# NRF52840_MICRO.net
KiCad netlist of a schematic drawn in Altium Designer
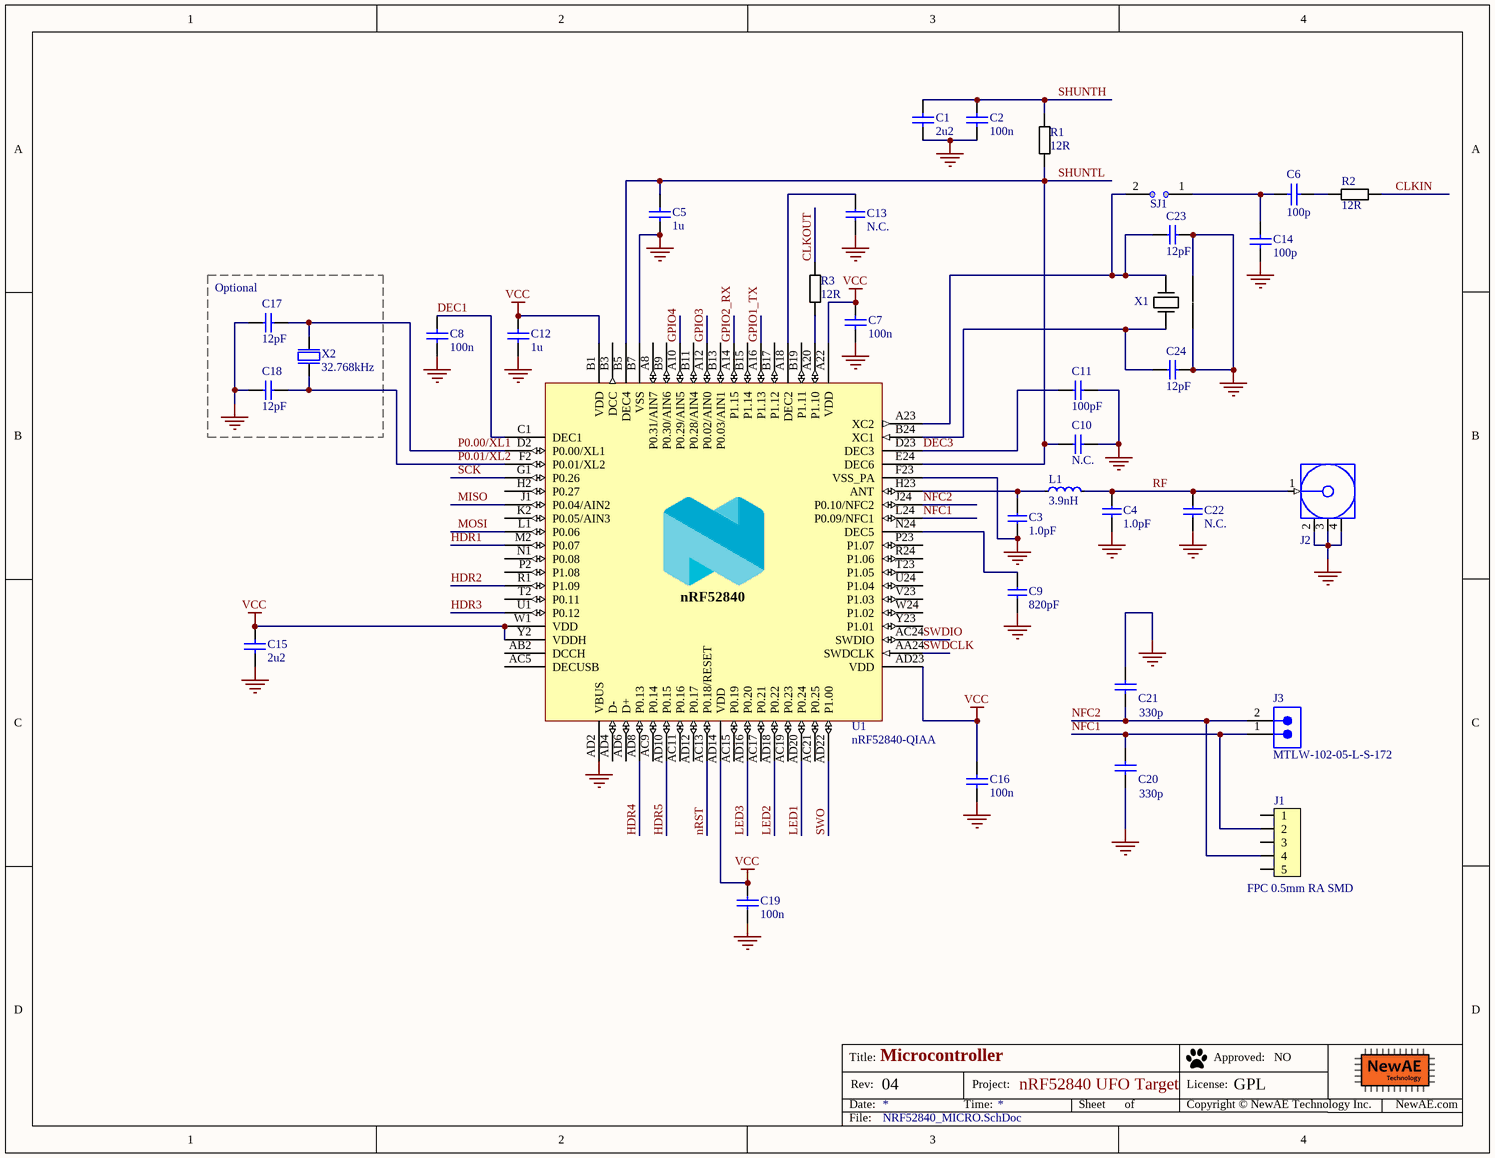
[diagram p0: NRF52840_MICRO.SchDoc]

(export (version "E")
  (design (tool "Eeschema 10.0.6"))
  (components
    (comp (ref "C1")
      (value "2u2")
      (footprint "CAPC0603_M")
      (description "2u2, 0603")
      (fields (field (name "PART NUMBER") "CCHIP-2u2-0603"))
      (libsource (lib "NewAE_AltiumLib") (part "CAP"))
    )
    (comp (ref "C2")
      (value "100n")
      (footprint "CAPC0603_M")
      (description "100n, 0603")
      (fields (field (name "PART NUMBER") "CCHIP-100n-0603"))
      (libsource (lib "NewAE_AltiumLib") (part "CAP"))
    )
    (comp (ref "C3")
      (value "1.0pF")
      (footprint "CAPC1005X04L")
      (description "Capacitor, NP0, ±5%")
      (fields (field (name "PART NUMBER") "C0402-1.0p") (field (name "PUBLISHER") "Nordic Semiconductor"))
      (libsource (lib "Nordic Passive DB") (part "CAP"))
    )
    (comp (ref "C4")
      (value "1.0pF")
      (footprint "CAPC1005X04L")
      (description "Capacitor, NP0, ±5%")
      (fields (field (name "PART NUMBER") "C0402-1.0p") (field (name "PUBLISHER") "Nordic Semiconductor"))
      (libsource (lib "Nordic Passive DB") (part "CAP"))
    )
    (comp (ref "C5")
      (value "1u")
      (footprint "CAPC0603_M")
      (description "1u, 0603, 50V")
      (fields (field (name "PART NUMBER") "CCHIP-1u-0603"))
      (libsource (lib "NewAE_AltiumLib") (part "CAP"))
    )
    (comp (ref "C6")
      (value "100p")
      (footprint "CAPC0603_M")
      (description "100p, 0603")
      (fields (field (name "PART NUMBER") "CCHIP-100p-0603"))
      (libsource (lib "NewAE_AltiumLib") (part "CAP"))
    )
    (comp (ref "C7")
      (value "100n")
      (footprint "CAPC0603_M")
      (description "100n, 0603")
      (fields (field (name "PART NUMBER") "CCHIP-100n-0603"))
      (libsource (lib "NewAE_AltiumLib") (part "CAP"))
    )
    (comp (ref "C8")
      (value "100n")
      (footprint "CAPC0603_M")
      (description "100n, 0603")
      (fields (field (name "PART NUMBER") "CCHIP-100n-0603"))
      (libsource (lib "NewAE_AltiumLib") (part "CAP"))
    )
    (comp (ref "C9")
      (value "820pF")
      (footprint "CAPC1005X04L")
      (description "Capacitor, NP0, ±5%")
      (fields (field (name "PART NUMBER") "C0402-820p") (field (name "PUBLISHER") "Nordic Semiconductor"))
      (libsource (lib "Nordic Passive DB") (part "CAP"))
    )
    (comp (ref "C10")
      (value "N.C.")
      (footprint "CAPC1005X04L")
      (description "Not mounted")
      (fields (field (name "PART NUMBER") "C0402-N.C.") (field (name "PUBLISHER") "Nordic Semiconductor"))
      (libsource (lib "Nordic Passive DB") (part "CAP"))
    )
    (comp (ref "C11")
      (value "100pF")
      (footprint "CAPC1005X04L")
      (description "Capacitor, NP0, ±5%")
      (fields (field (name "PART NUMBER") "C0402-100p") (field (name "PUBLISHER") "Nordic Semiconductor"))
      (libsource (lib "Nordic Passive DB") (part "CAP"))
    )
    (comp (ref "C12")
      (value "1u")
      (footprint "CAPC0603_M")
      (description "1u, 0603, 50V")
      (fields (field (name "PART NUMBER") "CCHIP-1u-0603"))
      (libsource (lib "NewAE_AltiumLib") (part "CAP"))
    )
    (comp (ref "C13")
      (value "N.C.")
      (footprint "CAPC1005X04L")
      (description "Not mounted")
      (fields (field (name "PART NUMBER") "C0402-N.C.") (field (name "PUBLISHER") "Nordic Semiconductor"))
      (libsource (lib "Nordic Passive DB") (part "CAP"))
    )
    (comp (ref "C14")
      (value "100p")
      (footprint "CAPC0603_M")
      (description "100p, 0603")
      (fields (field (name "PART NUMBER") "CCHIP-100p-0603"))
      (libsource (lib "NewAE_AltiumLib") (part "CAP"))
    )
    (comp (ref "C15")
      (value "2u2")
      (footprint "CAPC0603_M")
      (description "2u2, 0603")
      (fields (field (name "PART NUMBER") "CCHIP-2u2-0603"))
      (libsource (lib "NewAE_AltiumLib") (part "CAP"))
    )
    (comp (ref "C16")
      (value "100n")
      (footprint "CAPC0603_M")
      (description "100n, 0603")
      (fields (field (name "PART NUMBER") "CCHIP-100n-0603"))
      (libsource (lib "NewAE_AltiumLib") (part "CAP"))
    )
    (comp (ref "C17")
      (value "12pF")
      (footprint "CAPC1005X04L")
      (description "Capacitor, NP0, ±2%")
      (fields (field (name "PART NUMBER") "C0402-12p") (field (name "PUBLISHER") "Nordic Semiconductor"))
      (libsource (lib "Nordic Passive DB") (part "CAP"))
    )
    (comp (ref "C18")
      (value "12pF")
      (footprint "CAPC1005X04L")
      (description "Capacitor, NP0, ±2%")
      (fields (field (name "PART NUMBER") "C0402-12p") (field (name "PUBLISHER") "Nordic Semiconductor"))
      (libsource (lib "Nordic Passive DB") (part "CAP"))
    )
    (comp (ref "C19")
      (value "100n")
      (footprint "CAPC0603_M")
      (description "100n, 0603")
      (fields (field (name "PART NUMBER") "CCHIP-100n-0603"))
      (libsource (lib "NewAE_AltiumLib") (part "CAP"))
    )
    (comp (ref "C20")
      (value "330p")
      (footprint "RESC1608X55N")
      (description "CAP CER 330PF 100V X7R 0603")
      (fields (field (name "PART NUMBER") "CCHIP-330P-0603-100V") (field (name "TOLERANCE") "±10%"))
      (libsource (lib "NewAE_AltiumLib") (part "CAP"))
    )
    (comp (ref "C21")
      (value "330p")
      (footprint "RESC1608X55N")
      (description "CAP CER 330PF 100V X7R 0603")
      (fields (field (name "PART NUMBER") "CCHIP-330P-0603-100V") (field (name "TOLERANCE") "±10%"))
      (libsource (lib "NewAE_AltiumLib") (part "CAP"))
    )
    (comp (ref "C22")
      (value "N.C.")
      (footprint "CAPC1005X04L")
      (description "Not mounted")
      (fields (field (name "PART NUMBER") "C0402-N.C.") (field (name "PUBLISHER") "Nordic Semiconductor"))
      (libsource (lib "Nordic Passive DB") (part "CAP"))
    )
    (comp (ref "C23")
      (value "12pF")
      (footprint "CAPC1005X04L")
      (description "Capacitor, NP0, ±2%")
      (fields (field (name "PART NUMBER") "C0402-12p") (field (name "PUBLISHER") "Nordic Semiconductor"))
      (libsource (lib "Nordic Passive DB") (part "CAP"))
    )
    (comp (ref "C24")
      (value "12pF")
      (footprint "CAPC1005X04L")
      (description "Capacitor, NP0, ±2%")
      (fields (field (name "PART NUMBER") "C0402-12p") (field (name "PUBLISHER") "Nordic Semiconductor"))
      (libsource (lib "Nordic Passive DB") (part "CAP"))
    )
    (comp (ref "J1")
      (value "FPC 0.5mm RA SMD")
      (footprint "FPC_05P-0.5mm-RA-SMD")
      (description "0.5mm FPC, 5P,Right Angle SMT,Double Contact,H=1.2mm,White, Tin plated")
      (fields
        (field (name "PART NUMBER") "FPC_05P-0.5mm-RA-SMD")
        (field (name "MANUFACTURER") "W-CON")
        (field (name "PUBLISHER") "Nordic Semiconductor")
      )
      (libsource (lib "Nordic Passive DB") (part "CONN-5"))
    )
    (comp (ref "J2")
      (value "0734120110")
      (footprint "0734120110")
      (description "UMC RCPT STR 50 OHM SMD")
      (fields (field (name "PART NUMBER") "UMC_MALE"))
      (libsource (lib "NewAE_AltiumLib") (part "CON-RF-3GND"))
    )
    (comp (ref "J3")
      (value "MTLW-102-05-L-S-172")
      (footprint "SMTC-MTLW-102-05-X-S-172")
      (fields (field (name "MANUFACTURER") "Samtec"))
      (libsource (lib "Altium Content Vault") (part "SMTC-MTLW-102-05-X-S-172"))
    )
    (comp (ref "L1")
      (value "3.9nH")
      (footprint "INDC1005X04L")
      (description "High frequency chip inductor ±5%")
      (fields (field (name "PART NUMBER") "L0402-3n9") (field (name "PUBLISHER") "Nordic Semiconductor"))
      (libsource (lib "Nordic Passive DB") (part "IND"))
    )
    (comp (ref "R1")
      (value "12R")
      (footprint "RESC1608X55N")
      (description "12R res, 0603, 1%, 1/10W")
      (fields (field (name "PART NUMBER") "RCHIP-12R-0603") (field (name "TOLERANCE") "1%"))
      (libsource (lib "") (part "RES-EU_2"))
    )
    (comp (ref "R2")
      (value "12R")
      (footprint "RESC1608X55N")
      (description "12R res, 0603, 1%, 1/10W")
      (fields (field (name "PART NUMBER") "RCHIP-12R-0603") (field (name "TOLERANCE") "1%"))
      (libsource (lib "") (part "RES-EU_1"))
    )
    (comp (ref "R3")
      (value "12R")
      (footprint "RESC1608X55N")
      (description "12R res, 0603, 1%, 1/10W")
      (fields (field (name "PART NUMBER") "RCHIP-12R-0603") (field (name "TOLERANCE") "1%"))
      (libsource (lib "NewAE_AltiumLib") (part "RES-EU"))
    )
    (comp (ref "SJ1")
      (value "NO")
      (footprint "SJ_2S_NO")
      (description "Solder Jumper, NO")
      (fields (field (name "PART NUMBER") "SJ_2S_NO"))
      (libsource (lib "NewAE_AltiumLib") (part "SJ_2S_NO"))
    )
    (comp (ref "U1")
      (value "nRF52840-QIAA")
      (footprint "AQFN50P700X700X85_HS-74N")
      (description "Multi-protocol Bluetooth Low Energy, IEEE 802.15.4, ANT and 2.4GHz proprietary system-on-chip")
      (fields
        (field (name "PART NUMBER") "nRF52840-QIAAC0")
        (field (name "MANUFACTURER") "Nordic Semiconductor")
        (field (name "PUBLISHER") "Nordic Semiconductor")
      )
      (libsource (lib "Nordic Active DB") (part "nRF52840_QIAA"))
    )
    (comp (ref "X1")
      (value "ABM10AIG-32.000MHZ-4Z-T3")
      (footprint "2.5x2mm XTAL")
      (description "32MHz, SMD")
      (libsource (lib "NewAE_AltiumLib") (part "XTAL_4PIN_13"))
    )
    (comp (ref "X2")
      (value "32.768kHz")
      (footprint "XTAL_3215")
      (description "XTAL SMD 3215, 32.768kHz, Cl=9pF, Total Tol: ±50ppm")
      (fields
        (field (name "PART NUMBER") "XTAL_SMD3215_32.768kHz_9pF_General")
        (field (name "PUBLISHER") "Nordic Semiconductor")
      )
      (libsource (lib "Nordic Discrete DB") (part "XTAL_2-pin"))
    )
  )
  (nets
    (net (code "1") (name "/CLKIN") (class "Default")
      (node (ref "R2") (pin "2") (pinfunction "2_2") (pintype "passive"))
    )
    (net (code "2") (name "/CLKOUT") (class "Default")
      (node (ref "R3") (pin "2") (pinfunction "2_2") (pintype "passive"))
    )
    (net (code "3") (name "/DEC1") (class "Default")
      (node (ref "C8") (pin "1") (pinfunction "1_1") (pintype "passive"))
      (node (ref "U1") (pin "C1") (pinfunction "DEC1_C1") (pintype "power_in"))
    )
    (net (code "4") (name "/DEC3") (class "Default")
      (node (ref "C11") (pin "1") (pinfunction "1_1") (pintype "passive"))
      (node (ref "U1") (pin "D23") (pinfunction "DEC3_D23") (pintype "power_in"))
    )
    (net (code "5") (name "/GPIO1_TX") (class "Default")
      (node (ref "U1") (pin "A16") (pinfunction "P1.13_A16") (pintype "bidirectional"))
    )
    (net (code "6") (name "/GPIO2_RX") (class "Default")
      (node (ref "U1") (pin "A14") (pinfunction "P1.15_A14") (pintype "bidirectional"))
    )
    (net (code "7") (name "/GPIO3") (class "Default")
      (node (ref "U1") (pin "A12") (pinfunction "P0.02/AIN0_A12") (pintype "bidirectional"))
    )
    (net (code "8") (name "/GPIO4") (class "Default")
      (node (ref "U1") (pin "A10") (pinfunction "P0.29/AIN5_A10") (pintype "bidirectional"))
    )
    (net (code "9") (name "/HDR1") (class "Default")
      (node (ref "U1") (pin "M2") (pinfunction "P0.07_M2") (pintype "bidirectional"))
    )
    (net (code "10") (name "/HDR2") (class "Default")
      (node (ref "U1") (pin "R1") (pinfunction "P1.09_R1") (pintype "bidirectional"))
    )
    (net (code "11") (name "/HDR3") (class "Default")
      (node (ref "U1") (pin "U1") (pinfunction "P0.12_U1") (pintype "bidirectional"))
    )
    (net (code "12") (name "/HDR4") (class "Default")
      (node (ref "U1") (pin "AD8") (pinfunction "P0.13_AD8") (pintype "bidirectional"))
    )
    (net (code "13") (name "/HDR5") (class "Default")
      (node (ref "U1") (pin "AD10") (pinfunction "P0.15_AD10") (pintype "bidirectional"))
    )
    (net (code "14") (name "/LED1") (class "Default")
      (node (ref "U1") (pin "AD20") (pinfunction "P0.24_AD20") (pintype "bidirectional"))
    )
    (net (code "15") (name "/LED2") (class "Default")
      (node (ref "U1") (pin "AD18") (pinfunction "P0.22_AD18") (pintype "bidirectional"))
    )
    (net (code "16") (name "/LED3") (class "Default")
      (node (ref "U1") (pin "AD16") (pinfunction "P0.20_AD16") (pintype "bidirectional"))
    )
    (net (code "17") (name "/MISO") (class "Default")
      (node (ref "U1") (pin "J1") (pinfunction "P0.04/AIN2_J1") (pintype "bidirectional"))
    )
    (net (code "18") (name "/MOSI") (class "Default")
      (node (ref "U1") (pin "L1") (pinfunction "P0.06_L1") (pintype "bidirectional"))
    )
    (net (code "19") (name "/NFC1") (class "Default")
      (node (ref "C20") (pin "1") (pinfunction "1_1") (pintype "passive"))
      (node (ref "J1") (pin "2") (pinfunction "2_2") (pintype "passive"))
      (node (ref "J3") (pin "1") (pinfunction "1_1") (pintype "passive"))
      (node (ref "U1") (pin "L24") (pinfunction "P0.09/NFC1_L24") (pintype "bidirectional"))
    )
    (net (code "20") (name "/NFC2") (class "Default")
      (node (ref "C21") (pin "2") (pinfunction "2_2") (pintype "passive"))
      (node (ref "J1") (pin "4") (pinfunction "4_4") (pintype "passive"))
      (node (ref "J3") (pin "2") (pinfunction "2_2") (pintype "passive"))
      (node (ref "U1") (pin "J24") (pinfunction "P0.10/NFC2_J24") (pintype "bidirectional"))
    )
    (net (code "21") (name "/P0.00{slash}XL1") (class "Default")
      (node (ref "C17") (pin "1") (pinfunction "1_1") (pintype "passive"))
      (node (ref "U1") (pin "D2") (pinfunction "P0.00/XL1_D2") (pintype "bidirectional"))
      (node (ref "X2") (pin "1") (pinfunction "inp_1") (pintype "passive"))
    )
    (net (code "22") (name "/P0.01{slash}XL2") (class "Default")
      (node (ref "C18") (pin "1") (pinfunction "1_1") (pintype "passive"))
      (node (ref "U1") (pin "F2") (pinfunction "P0.01/XL2_F2") (pintype "bidirectional"))
      (node (ref "X2") (pin "2") (pinfunction "out_2") (pintype "passive"))
    )
    (net (code "23") (name "/RF") (class "Default")
      (node (ref "C22") (pin "1") (pinfunction "1_1") (pintype "passive"))
      (node (ref "C4") (pin "2") (pinfunction "2_2") (pintype "passive"))
      (node (ref "J2") (pin "1") (pinfunction "Signal_1") (pintype "input"))
      (node (ref "L1") (pin "2") (pinfunction "2_2") (pintype "passive"))
    )
    (net (code "24") (name "/SCK") (class "Default")
      (node (ref "U1") (pin "G1") (pinfunction "P0.26_G1") (pintype "bidirectional"))
    )
    (net (code "25") (name "/SHUNTH") (class "Default")
      (node (ref "C1") (pin "1") (pinfunction "1_1") (pintype "passive"))
      (node (ref "C2") (pin "1") (pinfunction "1_1") (pintype "passive"))
      (node (ref "R1") (pin "1") (pinfunction "1_1") (pintype "passive"))
    )
    (net (code "26") (name "/SHUNTL") (class "Default")
      (node (ref "C10") (pin "2") (pinfunction "2_2") (pintype "passive"))
      (node (ref "C5") (pin "1") (pinfunction "1_1") (pintype "passive"))
      (node (ref "R1") (pin "2") (pinfunction "2_2") (pintype "passive"))
      (node (ref "U1") (pin "B5") (pinfunction "DEC4_B5") (pintype "power_in"))
      (node (ref "U1") (pin "E24") (pinfunction "DEC6_E24") (pintype "power_in"))
    )
    (net (code "27") (name "/SWDCLK") (class "Default")
      (node (ref "U1") (pin "AA24") (pinfunction "SWDCLK_AA24") (pintype "input"))
    )
    (net (code "28") (name "/SWDIO") (class "Default")
      (node (ref "U1") (pin "AC24") (pinfunction "SWDIO_AC24") (pintype "bidirectional"))
    )
    (net (code "29") (name "/SWO") (class "Default")
      (node (ref "U1") (pin "AD22") (pinfunction "P1.00_AD22") (pintype "bidirectional"))
    )
    (net (code "30") (name "/nRST") (class "Default")
      (node (ref "U1") (pin "AC13") (pinfunction "P0.18/RESET_AC13") (pintype "bidirectional"))
    )
    (net (code "31") (name "GND") (class "Default")
      (node (ref "C1") (pin "2") (pinfunction "2_2") (pintype "passive"))
      (node (ref "C10") (pin "1") (pinfunction "1_1") (pintype "passive"))
      (node (ref "C11") (pin "2") (pinfunction "2_2") (pintype "passive"))
      (node (ref "C12") (pin "2") (pinfunction "2_2") (pintype "passive"))
      (node (ref "C13") (pin "2") (pinfunction "2_2") (pintype "passive"))
      (node (ref "C14") (pin "2") (pinfunction "2_2") (pintype "passive"))
      (node (ref "C15") (pin "2") (pinfunction "2_2") (pintype "passive"))
      (node (ref "C16") (pin "2") (pinfunction "2_2") (pintype "passive"))
      (node (ref "C17") (pin "2") (pinfunction "2_2") (pintype "passive"))
      (node (ref "C18") (pin "2") (pinfunction "2_2") (pintype "passive"))
      (node (ref "C19") (pin "2") (pinfunction "2_2") (pintype "passive"))
      (node (ref "C2") (pin "2") (pinfunction "2_2") (pintype "passive"))
      (node (ref "C20") (pin "2") (pinfunction "2_2") (pintype "passive"))
      (node (ref "C21") (pin "1") (pinfunction "1_1") (pintype "passive"))
      (node (ref "C22") (pin "2") (pinfunction "2_2") (pintype "passive"))
      (node (ref "C23") (pin "2") (pinfunction "2_2") (pintype "passive"))
      (node (ref "C24") (pin "2") (pinfunction "2_2") (pintype "passive"))
      (node (ref "C3") (pin "1") (pinfunction "1_1") (pintype "passive"))
      (node (ref "C4") (pin "1") (pinfunction "1_1") (pintype "passive"))
      (node (ref "C5") (pin "2") (pinfunction "2_2") (pintype "passive"))
      (node (ref "C7") (pin "2") (pinfunction "2_2") (pintype "passive"))
      (node (ref "C8") (pin "2") (pinfunction "2_2") (pintype "passive"))
      (node (ref "C9") (pin "2") (pinfunction "2_2") (pintype "passive"))
      (node (ref "J2") (pin "2") (pinfunction "GND_2") (pintype "power_in"))
      (node (ref "J2") (pin "3") (pinfunction "GND_3") (pintype "power_in"))
      (node (ref "J2") (pin "4") (pinfunction "GND_4") (pintype "power_in"))
      (node (ref "U1") (pin "74") (pinfunction "GND_74") (pintype "power_in"))
      (node (ref "U1") (pin "AD2") (pinfunction "VBUS_AD2") (pintype "power_in"))
      (node (ref "U1") (pin "B7") (pinfunction "VSS_B7") (pintype "power_in"))
      (node (ref "U1") (pin "F23") (pinfunction "VSS_PA_F23") (pintype "power_in"))
      (node (ref "X1") (pin "2") (pinfunction "GND_2") (pintype "power_in"))
      (node (ref "X1") (pin "4") (pinfunction "GND_4") (pintype "power_in"))
    )
    (net (code "32") (name "Net-(C6-Pad2)") (class "Default")
      (node (ref "C6") (pin "2") (pinfunction "2_2") (pintype "passive"))
      (node (ref "R2") (pin "1") (pinfunction "1_1") (pintype "passive"))
    )
    (net (code "33") (name "Net-(C14-Pad1)") (class "Default")
      (node (ref "C14") (pin "1") (pinfunction "1_1") (pintype "passive"))
      (node (ref "C6") (pin "1") (pinfunction "1_1") (pintype "passive"))
      (node (ref "SJ1") (pin "1") (pinfunction "1_1") (pintype "passive"))
    )
    (net (code "34") (name "Net-(U1-ANT)") (class "Default")
      (node (ref "C3") (pin "2") (pinfunction "2_2") (pintype "passive"))
      (node (ref "L1") (pin "1") (pinfunction "1_1") (pintype "passive"))
      (node (ref "U1") (pin "H23") (pinfunction "ANT_H23") (pintype "bidirectional"))
    )
    (net (code "35") (name "Net-(U1-DEC2)") (class "Default")
      (node (ref "C13") (pin "1") (pinfunction "1_1") (pintype "passive"))
      (node (ref "U1") (pin "A18") (pinfunction "DEC2_A18") (pintype "power_in"))
    )
    (net (code "36") (name "Net-(U1-DEC5)") (class "Default")
      (node (ref "C9") (pin "1") (pinfunction "1_1") (pintype "passive"))
      (node (ref "U1") (pin "N24") (pinfunction "DEC5_N24") (pintype "power_in"))
    )
    (net (code "37") (name "Net-(U1-P1.10)") (class "Default")
      (node (ref "R3") (pin "1") (pinfunction "1_1") (pintype "passive"))
      (node (ref "U1") (pin "A20") (pinfunction "P1.10_A20") (pintype "bidirectional"))
    )
    (net (code "38") (name "Net-(U1-XC1)") (class "Default")
      (node (ref "C24") (pin "1") (pinfunction "1_1") (pintype "passive"))
      (node (ref "U1") (pin "B24") (pinfunction "XC1_B24") (pintype "input"))
      (node (ref "X1") (pin "3") (pinfunction "OUT_3") (pintype "passive"))
    )
    (net (code "39") (name "Net-(U1-XC2)") (class "Default")
      (node (ref "C23") (pin "1") (pinfunction "1_1") (pintype "passive"))
      (node (ref "SJ1") (pin "2") (pinfunction "2_2") (pintype "passive"))
      (node (ref "U1") (pin "A23") (pinfunction "XC2_A23") (pintype "output"))
      (node (ref "X1") (pin "1") (pinfunction "IN_1") (pintype "passive"))
    )
    (net (code "40") (name "VCC") (class "Default")
      (node (ref "C12") (pin "1") (pinfunction "1_1") (pintype "passive"))
      (node (ref "C15") (pin "1") (pinfunction "1_1") (pintype "passive"))
      (node (ref "C16") (pin "1") (pinfunction "1_1") (pintype "passive"))
      (node (ref "C19") (pin "1") (pinfunction "1_1") (pintype "passive"))
      (node (ref "C7") (pin "1") (pinfunction "1_1") (pintype "passive"))
      (node (ref "U1") (pin "A22") (pinfunction "VDD_A22") (pintype "power_in"))
      (node (ref "U1") (pin "AD14") (pinfunction "VDD_AD14") (pintype "power_in"))
      (node (ref "U1") (pin "AD23") (pinfunction "VDD_AD23") (pintype "power_in"))
      (node (ref "U1") (pin "B1") (pinfunction "VDD_B1") (pintype "power_in"))
      (node (ref "U1") (pin "W1") (pinfunction "VDD_W1") (pintype "power_in"))
      (node (ref "U1") (pin "Y2") (pinfunction "VDDH_Y2") (pintype "power_in"))
    )
    (net (code "41") (name "unconnected-(J1-Pad1)") (class "Default")
      (node (ref "J1") (pin "1") (pinfunction "1_1") (pintype "passive"))
    )
    (net (code "42") (name "unconnected-(J1-Pad3)") (class "Default")
      (node (ref "J1") (pin "3") (pinfunction "3_3") (pintype "passive"))
    )
    (net (code "43") (name "unconnected-(J1-Pad5)") (class "Default")
      (node (ref "J1") (pin "5") (pinfunction "5_5") (pintype "passive"))
    )
    (net (code "44") (name "unconnected-(U1-D+-PadAD6)") (class "Default")
      (node (ref "U1") (pin "AD6") (pinfunction "D+_AD6") (pintype "bidirectional"))
    )
    (net (code "45") (name "unconnected-(U1-D--PadAD4)") (class "Default")
      (node (ref "U1") (pin "AD4") (pinfunction "D-_AD4") (pintype "bidirectional"))
    )
    (net (code "46") (name "unconnected-(U1-DCC-PadB3)") (class "Default")
      (node (ref "U1") (pin "B3") (pinfunction "DCC_B3") (pintype "output"))
    )
    (net (code "47") (name "unconnected-(U1-DCCH-PadAB2)") (class "Default")
      (node (ref "U1") (pin "AB2") (pinfunction "DCCH_AB2") (pintype "power_in"))
    )
    (net (code "48") (name "unconnected-(U1-DECUSB-PadAC5)") (class "Default")
      (node (ref "U1") (pin "AC5") (pinfunction "DECUSB_AC5") (pintype "power_in"))
    )
    (net (code "49") (name "unconnected-(U1-P0.03{slash}AIN1-PadB13)") (class "Default")
      (node (ref "U1") (pin "B13") (pinfunction "P0.03/AIN1_B13") (pintype "bidirectional"))
    )
    (net (code "50") (name "unconnected-(U1-P0.05{slash}AIN3-PadK2)") (class "Default")
      (node (ref "U1") (pin "K2") (pinfunction "P0.05/AIN3_K2") (pintype "bidirectional"))
    )
    (net (code "51") (name "unconnected-(U1-P0.08-PadN1)") (class "Default")
      (node (ref "U1") (pin "N1") (pinfunction "P0.08_N1") (pintype "bidirectional"))
    )
    (net (code "52") (name "unconnected-(U1-P0.11-PadT2)") (class "Default")
      (node (ref "U1") (pin "T2") (pinfunction "P0.11_T2") (pintype "bidirectional"))
    )
    (net (code "53") (name "unconnected-(U1-P0.14-PadAC9)") (class "Default")
      (node (ref "U1") (pin "AC9") (pinfunction "P0.14_AC9") (pintype "bidirectional"))
    )
    (net (code "54") (name "unconnected-(U1-P0.16-PadAC11)") (class "Default")
      (node (ref "U1") (pin "AC11") (pinfunction "P0.16_AC11") (pintype "bidirectional"))
    )
    (net (code "55") (name "unconnected-(U1-P0.17-PadAD12)") (class "Default")
      (node (ref "U1") (pin "AD12") (pinfunction "P0.17_AD12") (pintype "bidirectional"))
    )
    (net (code "56") (name "unconnected-(U1-P0.19-PadAC15)") (class "Default")
      (node (ref "U1") (pin "AC15") (pinfunction "P0.19_AC15") (pintype "bidirectional"))
    )
    (net (code "57") (name "unconnected-(U1-P0.21-PadAC17)") (class "Default")
      (node (ref "U1") (pin "AC17") (pinfunction "P0.21_AC17") (pintype "bidirectional"))
    )
    (net (code "58") (name "unconnected-(U1-P0.23-PadAC19)") (class "Default")
      (node (ref "U1") (pin "AC19") (pinfunction "P0.23_AC19") (pintype "bidirectional"))
    )
    (net (code "59") (name "unconnected-(U1-P0.25-PadAC21)") (class "Default")
      (node (ref "U1") (pin "AC21") (pinfunction "P0.25_AC21") (pintype "bidirectional"))
    )
    (net (code "60") (name "unconnected-(U1-P0.27-PadH2)") (class "Default")
      (node (ref "U1") (pin "H2") (pinfunction "P0.27_H2") (pintype "bidirectional"))
    )
    (net (code "61") (name "unconnected-(U1-P0.28{slash}AIN4-PadB11)") (class "Default")
      (node (ref "U1") (pin "B11") (pinfunction "P0.28/AIN4_B11") (pintype "bidirectional"))
    )
    (net (code "62") (name "unconnected-(U1-P0.30{slash}AIN6-PadB9)") (class "Default")
      (node (ref "U1") (pin "B9") (pinfunction "P0.30/AIN6_B9") (pintype "bidirectional"))
    )
    (net (code "63") (name "unconnected-(U1-P0.31{slash}AIN7-PadA8)") (class "Default")
      (node (ref "U1") (pin "A8") (pinfunction "P0.31/AIN7_A8") (pintype "bidirectional"))
    )
    (net (code "64") (name "unconnected-(U1-P1.01-PadY23)") (class "Default")
      (node (ref "U1") (pin "Y23") (pinfunction "P1.01_Y23") (pintype "bidirectional"))
    )
    (net (code "65") (name "unconnected-(U1-P1.02-PadW24)") (class "Default")
      (node (ref "U1") (pin "W24") (pinfunction "P1.02_W24") (pintype "bidirectional"))
    )
    (net (code "66") (name "unconnected-(U1-P1.03-PadV23)") (class "Default")
      (node (ref "U1") (pin "V23") (pinfunction "P1.03_V23") (pintype "bidirectional"))
    )
    (net (code "67") (name "unconnected-(U1-P1.04-PadU24)") (class "Default")
      (node (ref "U1") (pin "U24") (pinfunction "P1.04_U24") (pintype "bidirectional"))
    )
    (net (code "68") (name "unconnected-(U1-P1.05-PadT23)") (class "Default")
      (node (ref "U1") (pin "T23") (pinfunction "P1.05_T23") (pintype "bidirectional"))
    )
    (net (code "69") (name "unconnected-(U1-P1.06-PadR24)") (class "Default")
      (node (ref "U1") (pin "R24") (pinfunction "P1.06_R24") (pintype "bidirectional"))
    )
    (net (code "70") (name "unconnected-(U1-P1.07-PadP23)") (class "Default")
      (node (ref "U1") (pin "P23") (pinfunction "P1.07_P23") (pintype "bidirectional"))
    )
    (net (code "71") (name "unconnected-(U1-P1.08-PadP2)") (class "Default")
      (node (ref "U1") (pin "P2") (pinfunction "P1.08_P2") (pintype "bidirectional"))
    )
    (net (code "72") (name "unconnected-(U1-P1.11-PadB19)") (class "Default")
      (node (ref "U1") (pin "B19") (pinfunction "P1.11_B19") (pintype "bidirectional"))
    )
    (net (code "73") (name "unconnected-(U1-P1.12-PadB17)") (class "Default")
      (node (ref "U1") (pin "B17") (pinfunction "P1.12_B17") (pintype "bidirectional"))
    )
    (net (code "74") (name "unconnected-(U1-P1.14-PadB15)") (class "Default")
      (node (ref "U1") (pin "B15") (pinfunction "P1.14_B15") (pintype "bidirectional"))
    )
  )
)
